# tenacitas.net
KiCad netlist of a schematic drawn in EAGLE
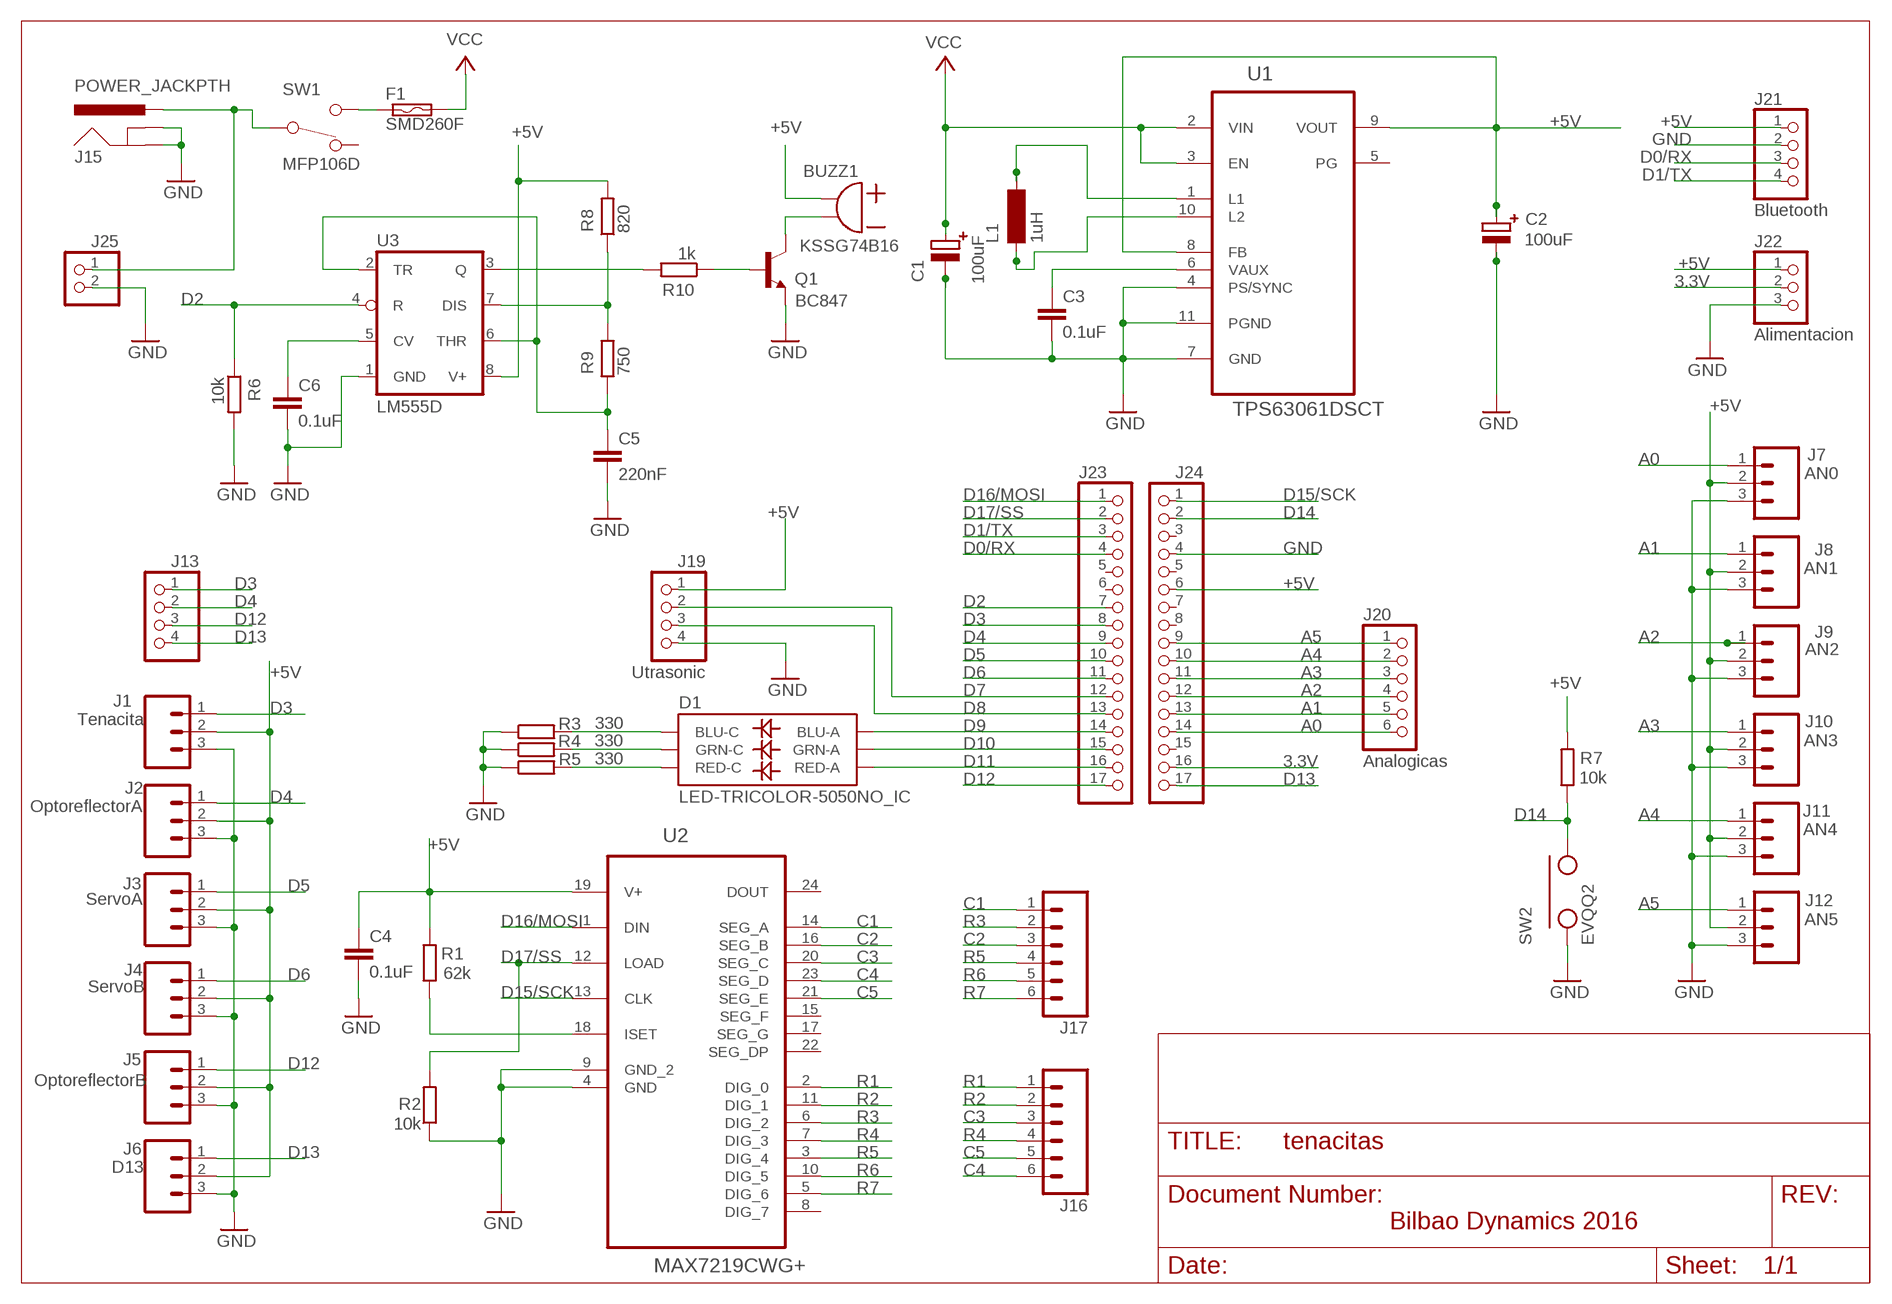
[diagram p0: schematic, sheet 1]

(export (version "E")
  (design (tool "Eeschema 10.0.6"))
  (components
    (comp (ref "BUZZ1")
      (value "KSSG74B16")
      (footprint "eagle-import:KSSG74B16")
      (libsource (lib "eagle-import") (part "KSSG74B16"))
    )
    (comp (ref "C1")
      (value "100uF")
      (footprint "eagle-import:EDK107M016A9G")
      (libsource (lib "eagle-import") (part "EDK107M016A9G"))
    )
    (comp (ref "C2")
      (value "100uF")
      (footprint "eagle-import:EDK107M016A9G")
      (libsource (lib "eagle-import") (part "EDK107M016A9G"))
    )
    (comp (ref "C3")
      (value "0.1uF")
      (footprint "eagle-import:C0805")
      (libsource (lib "eagle-import") (part "C-EUC0805"))
    )
    (comp (ref "C4")
      (value "0.1uF")
      (footprint "eagle-import:C0805")
      (libsource (lib "eagle-import") (part "C-EUC0805"))
    )
    (comp (ref "C5")
      (value "220nF")
      (footprint "eagle-import:C0805")
      (libsource (lib "eagle-import") (part "C-EUC0805"))
    )
    (comp (ref "C6")
      (value "0.1uF")
      (footprint "eagle-import:C0805")
      (libsource (lib "eagle-import") (part "C-EUC0805"))
    )
    (comp (ref "D1")
      (value "LED-TRICOLOR-5050NO_IC")
      (footprint "eagle-import:LED-TRICOLOR-5050")
      (libsource (lib "eagle-import") (part "LED-TRICOLOR-5050NO_IC"))
    )
    (comp (ref "F1")
      (value "SMD260F")
      (footprint "eagle-import:SMD050F")
      (libsource (lib "eagle-import") (part "SMDF260"))
    )
    (comp (ref "J1")
      (value "Tenacita")
      (footprint "eagle-import:1X03")
      (libsource (lib "eagle-import") (part "M03PTH"))
    )
    (comp (ref "J2")
      (value "OptoreflectorA")
      (footprint "eagle-import:1X03")
      (libsource (lib "eagle-import") (part "M03PTH"))
    )
    (comp (ref "J3")
      (value "ServoA")
      (footprint "eagle-import:1X03")
      (libsource (lib "eagle-import") (part "M03PTH"))
    )
    (comp (ref "J4")
      (value "ServoB")
      (footprint "eagle-import:1X03")
      (libsource (lib "eagle-import") (part "M03PTH"))
    )
    (comp (ref "J5")
      (value "OptoreflectorB")
      (footprint "eagle-import:1X03")
      (libsource (lib "eagle-import") (part "M03PTH"))
    )
    (comp (ref "J6")
      (value "D13")
      (footprint "eagle-import:1X03")
      (libsource (lib "eagle-import") (part "M03PTH"))
    )
    (comp (ref "J7")
      (value "AN0")
      (footprint "eagle-import:1X03")
      (libsource (lib "eagle-import") (part "M03PTH"))
    )
    (comp (ref "J8")
      (value "AN1")
      (footprint "eagle-import:1X03")
      (libsource (lib "eagle-import") (part "M03PTH"))
    )
    (comp (ref "J9")
      (value "AN2")
      (footprint "eagle-import:1X03")
      (libsource (lib "eagle-import") (part "M03PTH"))
    )
    (comp (ref "J10")
      (value "AN3")
      (footprint "eagle-import:1X03")
      (libsource (lib "eagle-import") (part "M03PTH"))
    )
    (comp (ref "J11")
      (value "AN4")
      (footprint "eagle-import:1X03")
      (libsource (lib "eagle-import") (part "M03PTH"))
    )
    (comp (ref "J12")
      (value "AN5")
      (footprint "eagle-import:1X03")
      (libsource (lib "eagle-import") (part "M03PTH"))
    )
    (comp (ref "J13")
      (value "PINHD-1X4")
      (footprint "eagle-import:1X04")
      (libsource (lib "eagle-import") (part "PINHD-1X4"))
    )
    (comp (ref "J15")
      (value "POWER_JACKPTH")
      (footprint "eagle-import:POWER_JACK_PTH")
      (libsource (lib "eagle-import") (part "POWER_JACKPTH"))
    )
    (comp (ref "J16")
      (value "M06SILK_FEMALE_PTH")
      (footprint "eagle-import:1X06")
      (libsource (lib "eagle-import") (part "M06SILK_FEMALE_PTH"))
    )
    (comp (ref "J17")
      (value "M06SILK_FEMALE_PTH")
      (footprint "eagle-import:1X06")
      (libsource (lib "eagle-import") (part "M06SILK_FEMALE_PTH"))
    )
    (comp (ref "J19")
      (value "Utrasonic")
      (footprint "eagle-import:1X04")
      (libsource (lib "eagle-import") (part "PINHD-1X4"))
    )
    (comp (ref "J20")
      (value "Analogicas")
      (footprint "eagle-import:1X06")
      (libsource (lib "eagle-import") (part "PINHD-1X6"))
    )
    (comp (ref "J21")
      (value "Bluetooth")
      (footprint "eagle-import:1X04")
      (libsource (lib "eagle-import") (part "PINHD-1X4"))
    )
    (comp (ref "J22")
      (value "Alimentacion")
      (footprint "eagle-import:1X03")
      (libsource (lib "eagle-import") (part "PINHD-1X3"))
    )
    (comp (ref "J23")
      (value "PINHD-1X17")
      (footprint "eagle-import:1X17")
      (libsource (lib "eagle-import") (part "PINHD-1X17"))
    )
    (comp (ref "J24")
      (value "PINHD-1X17")
      (footprint "eagle-import:1X17")
      (libsource (lib "eagle-import") (part "PINHD-1X17"))
    )
    (comp (ref "J25")
      (value "PINHD-1X2")
      (footprint "eagle-import:1X02")
      (libsource (lib "eagle-import") (part "PINHD-1X2"))
    )
    (comp (ref "L1")
      (value "1uH")
      (footprint "eagle-import:MCSDRH73B")
      (libsource (lib "eagle-import") (part "MCSDRH73B"))
    )
    (comp (ref "Q1")
      (value "BC847")
      (footprint "eagle-import:SOT23")
      (libsource (lib "eagle-import") (part "BC847"))
    )
    (comp (ref "R1")
      (value "62k")
      (footprint "eagle-import:R0805")
      (libsource (lib "eagle-import") (part "R-EU_R0805"))
    )
    (comp (ref "R2")
      (value "10k")
      (footprint "eagle-import:R0805")
      (libsource (lib "eagle-import") (part "R-EU_R0805"))
    )
    (comp (ref "R3")
      (value "330")
      (footprint "eagle-import:R0805")
      (libsource (lib "eagle-import") (part "R-EU_R0805"))
    )
    (comp (ref "R4")
      (value "330")
      (footprint "eagle-import:R0805")
      (libsource (lib "eagle-import") (part "R-EU_R0805"))
    )
    (comp (ref "R5")
      (value "330")
      (footprint "eagle-import:R0805")
      (libsource (lib "eagle-import") (part "R-EU_R0805"))
    )
    (comp (ref "R6")
      (value "10k")
      (footprint "eagle-import:R0805")
      (libsource (lib "eagle-import") (part "R-EU_R0805"))
    )
    (comp (ref "R7")
      (value "10k")
      (footprint "eagle-import:R0805")
      (libsource (lib "eagle-import") (part "R-EU_R0805"))
    )
    (comp (ref "R8")
      (value "820")
      (footprint "eagle-import:R0805")
      (libsource (lib "eagle-import") (part "R-EU_R0805"))
    )
    (comp (ref "R9")
      (value "750")
      (footprint "eagle-import:R0805")
      (libsource (lib "eagle-import") (part "R-EU_R0805"))
    )
    (comp (ref "R10")
      (value "1k")
      (footprint "eagle-import:R0805")
      (libsource (lib "eagle-import") (part "R-EU_R0805"))
    )
    (comp (ref "SW1")
      (value "MFP106D")
      (footprint "eagle-import:MFP106D")
      (libsource (lib "eagle-import") (part "MFP106D"))
    )
    (comp (ref "SW2")
      (value "EVQQ2")
      (footprint "eagle-import:JAEGGER_MKII_EVQQ2")
      (libsource (lib "eagle-import") (part "JAEGGER_MKII_EVQQ2"))
    )
    (comp (ref "U1")
      (value "TPS63061DSCT")
      (footprint "eagle-import:SON50P300X300X80-11N")
      (libsource (lib "eagle-import") (part "TPS63061DSCT"))
    )
    (comp (ref "U2")
      (value "MAX7219CWG+")
      (footprint "eagle-import:SOIC127P1032X265-24N")
      (libsource (lib "eagle-import") (part "MAX7219CWG+"))
    )
    (comp (ref "U3")
      (value "LM555D")
      (footprint "eagle-import:SO08")
      (libsource (lib "eagle-import") (part "555DLM"))
    )
  )
  (nets
    (net (code "1") (name "/+5V") (class "Default")
      (node (ref "BUZZ1") (pin "P$2") (pinfunction "2_P$2") (pintype "passive"))
      (node (ref "BUZZ1") (pin "P$3") (pinfunction "2_P$3") (pintype "passive"))
      (node (ref "C2") (pin "1") (pinfunction "1_1") (pintype "passive"))
      (node (ref "C4") (pin "1") (pinfunction "1_1") (pintype "passive"))
      (node (ref "J1") (pin "2") (pinfunction "2_2") (pintype "passive"))
      (node (ref "J10") (pin "2") (pinfunction "2_2") (pintype "passive"))
      (node (ref "J11") (pin "2") (pinfunction "2_2") (pintype "passive"))
      (node (ref "J12") (pin "2") (pinfunction "2_2") (pintype "passive"))
      (node (ref "J19") (pin "1") (pinfunction "1_1") (pintype "passive"))
      (node (ref "J2") (pin "2") (pinfunction "2_2") (pintype "passive"))
      (node (ref "J21") (pin "1") (pinfunction "1_1") (pintype "passive"))
      (node (ref "J22") (pin "1") (pinfunction "1_1") (pintype "passive"))
      (node (ref "J24") (pin "6") (pinfunction "6_6") (pintype "passive"))
      (node (ref "J3") (pin "2") (pinfunction "2_2") (pintype "passive"))
      (node (ref "J4") (pin "2") (pinfunction "2_2") (pintype "passive"))
      (node (ref "J5") (pin "2") (pinfunction "2_2") (pintype "passive"))
      (node (ref "J6") (pin "2") (pinfunction "2_2") (pintype "passive"))
      (node (ref "J7") (pin "2") (pinfunction "2_2") (pintype "passive"))
      (node (ref "J8") (pin "2") (pinfunction "2_2") (pintype "passive"))
      (node (ref "J9") (pin "2") (pinfunction "2_2") (pintype "passive"))
      (node (ref "R1") (pin "2") (pinfunction "2_2") (pintype "passive"))
      (node (ref "R7") (pin "2") (pinfunction "2_2") (pintype "passive"))
      (node (ref "R8") (pin "2") (pinfunction "2_2") (pintype "passive"))
      (node (ref "U1") (pin "8") (pinfunction "FB_8") (pintype "input"))
      (node (ref "U1") (pin "9") (pinfunction "VOUT_9") (pintype "output"))
      (node (ref "U2") (pin "19") (pinfunction "V+_19") (pintype "power_in"))
      (node (ref "U3") (pin "8") (pinfunction "V+_8") (pintype "power_in"))
    )
    (net (code "2") (name "/3.3V") (class "Default")
      (node (ref "J22") (pin "2") (pinfunction "2_2") (pintype "passive"))
      (node (ref "J24") (pin "16") (pinfunction "16_16") (pintype "passive"))
    )
    (net (code "3") (name "/A0") (class "Default")
      (node (ref "J20") (pin "6") (pinfunction "6_6") (pintype "passive"))
      (node (ref "J24") (pin "14") (pinfunction "14_14") (pintype "passive"))
      (node (ref "J7") (pin "1") (pinfunction "1_1") (pintype "passive"))
    )
    (net (code "4") (name "/A1") (class "Default")
      (node (ref "J20") (pin "5") (pinfunction "5_5") (pintype "passive"))
      (node (ref "J24") (pin "13") (pinfunction "13_13") (pintype "passive"))
      (node (ref "J8") (pin "1") (pinfunction "1_1") (pintype "passive"))
    )
    (net (code "5") (name "/A2") (class "Default")
      (node (ref "J20") (pin "4") (pinfunction "4_4") (pintype "passive"))
      (node (ref "J24") (pin "12") (pinfunction "12_12") (pintype "passive"))
      (node (ref "J9") (pin "1") (pinfunction "1_1") (pintype "passive"))
    )
    (net (code "6") (name "/A3") (class "Default")
      (node (ref "J10") (pin "1") (pinfunction "1_1") (pintype "passive"))
      (node (ref "J20") (pin "3") (pinfunction "3_3") (pintype "passive"))
      (node (ref "J24") (pin "11") (pinfunction "11_11") (pintype "passive"))
    )
    (net (code "7") (name "/A4") (class "Default")
      (node (ref "J11") (pin "1") (pinfunction "1_1") (pintype "passive"))
      (node (ref "J20") (pin "2") (pinfunction "2_2") (pintype "passive"))
      (node (ref "J24") (pin "10") (pinfunction "10_10") (pintype "passive"))
    )
    (net (code "8") (name "/A5") (class "Default")
      (node (ref "J12") (pin "1") (pinfunction "1_1") (pintype "passive"))
      (node (ref "J20") (pin "1") (pinfunction "1_1") (pintype "passive"))
      (node (ref "J24") (pin "9") (pinfunction "9_9") (pintype "passive"))
    )
    (net (code "9") (name "/C1") (class "Default")
      (node (ref "J17") (pin "1") (pinfunction "1_1") (pintype "passive"))
      (node (ref "U2") (pin "14") (pinfunction "SEG_A_14") (pintype "output"))
    )
    (net (code "10") (name "/C2") (class "Default")
      (node (ref "J17") (pin "3") (pinfunction "3_3") (pintype "passive"))
      (node (ref "U2") (pin "16") (pinfunction "SEG_B_16") (pintype "output"))
    )
    (net (code "11") (name "/C3") (class "Default")
      (node (ref "J16") (pin "3") (pinfunction "3_3") (pintype "passive"))
      (node (ref "U2") (pin "20") (pinfunction "SEG_C_20") (pintype "output"))
    )
    (net (code "12") (name "/C4") (class "Default")
      (node (ref "J16") (pin "6") (pinfunction "6_6") (pintype "passive"))
      (node (ref "U2") (pin "23") (pinfunction "SEG_D_23") (pintype "output"))
    )
    (net (code "13") (name "/C5") (class "Default")
      (node (ref "J16") (pin "5") (pinfunction "5_5") (pintype "passive"))
      (node (ref "U2") (pin "21") (pinfunction "SEG_E_21") (pintype "output"))
    )
    (net (code "14") (name "/D0{slash}RX") (class "Default")
      (node (ref "J21") (pin "3") (pinfunction "3_3") (pintype "passive"))
      (node (ref "J23") (pin "4") (pinfunction "4_4") (pintype "passive"))
    )
    (net (code "15") (name "/D1{slash}TX") (class "Default")
      (node (ref "J21") (pin "4") (pinfunction "4_4") (pintype "passive"))
      (node (ref "J23") (pin "3") (pinfunction "3_3") (pintype "passive"))
    )
    (net (code "16") (name "/D2") (class "Default")
      (node (ref "J23") (pin "7") (pinfunction "7_7") (pintype "passive"))
      (node (ref "R6") (pin "1") (pinfunction "1_1") (pintype "passive"))
      (node (ref "U3") (pin "4") (pinfunction "R_4") (pintype "input"))
    )
    (net (code "17") (name "/D3") (class "Default")
      (node (ref "J1") (pin "1") (pinfunction "1_1") (pintype "passive"))
      (node (ref "J13") (pin "1") (pinfunction "1_1") (pintype "passive"))
      (node (ref "J23") (pin "8") (pinfunction "8_8") (pintype "passive"))
    )
    (net (code "18") (name "/D4") (class "Default")
      (node (ref "J13") (pin "2") (pinfunction "2_2") (pintype "passive"))
      (node (ref "J2") (pin "1") (pinfunction "1_1") (pintype "passive"))
      (node (ref "J23") (pin "9") (pinfunction "9_9") (pintype "passive"))
    )
    (net (code "19") (name "/D5") (class "Default")
      (node (ref "J23") (pin "10") (pinfunction "10_10") (pintype "passive"))
      (node (ref "J3") (pin "1") (pinfunction "1_1") (pintype "passive"))
    )
    (net (code "20") (name "/D6") (class "Default")
      (node (ref "J23") (pin "11") (pinfunction "11_11") (pintype "passive"))
      (node (ref "J4") (pin "1") (pinfunction "1_1") (pintype "passive"))
    )
    (net (code "21") (name "/D7") (class "Default")
      (node (ref "J19") (pin "2") (pinfunction "2_2") (pintype "passive"))
      (node (ref "J23") (pin "12") (pinfunction "12_12") (pintype "passive"))
    )
    (net (code "22") (name "/D8") (class "Default")
      (node (ref "J19") (pin "3") (pinfunction "3_3") (pintype "passive"))
      (node (ref "J23") (pin "13") (pinfunction "13_13") (pintype "passive"))
    )
    (net (code "23") (name "/D9") (class "Default")
      (node (ref "D1") (pin "3") (pinfunction "BLU-A_3") (pintype "bidirectional"))
      (node (ref "J23") (pin "14") (pinfunction "14_14") (pintype "passive"))
    )
    (net (code "24") (name "/D10") (class "Default")
      (node (ref "D1") (pin "1") (pinfunction "GRN-A_1") (pintype "bidirectional"))
      (node (ref "J23") (pin "15") (pinfunction "15_15") (pintype "passive"))
    )
    (net (code "25") (name "/D11") (class "Default")
      (node (ref "D1") (pin "2") (pinfunction "RED-A_2") (pintype "bidirectional"))
      (node (ref "J23") (pin "16") (pinfunction "16_16") (pintype "passive"))
    )
    (net (code "26") (name "/D12") (class "Default")
      (node (ref "J13") (pin "3") (pinfunction "3_3") (pintype "passive"))
      (node (ref "J23") (pin "17") (pinfunction "17_17") (pintype "passive"))
      (node (ref "J5") (pin "1") (pinfunction "1_1") (pintype "passive"))
    )
    (net (code "27") (name "/D13") (class "Default")
      (node (ref "J13") (pin "4") (pinfunction "4_4") (pintype "passive"))
      (node (ref "J24") (pin "17") (pinfunction "17_17") (pintype "passive"))
      (node (ref "J6") (pin "1") (pinfunction "1_1") (pintype "passive"))
    )
    (net (code "28") (name "/D14") (class "Default")
      (node (ref "J24") (pin "2") (pinfunction "2_2") (pintype "passive"))
      (node (ref "R7") (pin "1") (pinfunction "1_1") (pintype "passive"))
      (node (ref "SW2") (pin "P$1") (pinfunction "P$2_P$1") (pintype "passive"))
      (node (ref "SW2") (pin "P$4") (pinfunction "P$2_P$4") (pintype "passive"))
    )
    (net (code "29") (name "/D15{slash}SCK") (class "Default")
      (node (ref "J24") (pin "1") (pinfunction "1_1") (pintype "passive"))
      (node (ref "U2") (pin "13") (pinfunction "CLK_13") (pintype "input"))
    )
    (net (code "30") (name "/D16{slash}MOSI") (class "Default")
      (node (ref "J23") (pin "1") (pinfunction "1_1") (pintype "passive"))
      (node (ref "U2") (pin "1") (pinfunction "DIN_1") (pintype "input"))
    )
    (net (code "31") (name "/D17{slash}SS") (class "Default")
      (node (ref "J23") (pin "2") (pinfunction "2_2") (pintype "passive"))
      (node (ref "R2") (pin "2") (pinfunction "2_2") (pintype "passive"))
      (node (ref "U2") (pin "12") (pinfunction "LOAD_12") (pintype "input"))
    )
    (net (code "32") (name "/R1") (class "Default")
      (node (ref "J16") (pin "1") (pinfunction "1_1") (pintype "passive"))
      (node (ref "U2") (pin "2") (pinfunction "DIG_0_2") (pintype "output"))
    )
    (net (code "33") (name "/R2") (class "Default")
      (node (ref "J16") (pin "2") (pinfunction "2_2") (pintype "passive"))
      (node (ref "U2") (pin "11") (pinfunction "DIG_1_11") (pintype "output"))
    )
    (net (code "34") (name "/R3") (class "Default")
      (node (ref "J17") (pin "2") (pinfunction "2_2") (pintype "passive"))
      (node (ref "U2") (pin "6") (pinfunction "DIG_2_6") (pintype "output"))
    )
    (net (code "35") (name "/R4") (class "Default")
      (node (ref "J16") (pin "4") (pinfunction "4_4") (pintype "passive"))
      (node (ref "U2") (pin "7") (pinfunction "DIG_3_7") (pintype "output"))
    )
    (net (code "36") (name "/R5") (class "Default")
      (node (ref "J17") (pin "4") (pinfunction "4_4") (pintype "passive"))
      (node (ref "U2") (pin "3") (pinfunction "DIG_4_3") (pintype "output"))
    )
    (net (code "37") (name "/R6") (class "Default")
      (node (ref "J17") (pin "5") (pinfunction "5_5") (pintype "passive"))
      (node (ref "U2") (pin "10") (pinfunction "DIG_5_10") (pintype "output"))
    )
    (net (code "38") (name "/R7") (class "Default")
      (node (ref "J17") (pin "6") (pinfunction "6_6") (pintype "passive"))
      (node (ref "U2") (pin "5") (pinfunction "DIG_6_5") (pintype "output"))
    )
    (net (code "39") (name "GND") (class "Default")
      (node (ref "C1") (pin "2") (pinfunction "2_2") (pintype "passive"))
      (node (ref "C2") (pin "2") (pinfunction "2_2") (pintype "passive"))
      (node (ref "C3") (pin "2") (pinfunction "2_2") (pintype "passive"))
      (node (ref "C4") (pin "2") (pinfunction "2_2") (pintype "passive"))
      (node (ref "C5") (pin "2") (pinfunction "2_2") (pintype "passive"))
      (node (ref "C6") (pin "2") (pinfunction "2_2") (pintype "passive"))
      (node (ref "J1") (pin "3") (pinfunction "3_3") (pintype "passive"))
      (node (ref "J10") (pin "3") (pinfunction "3_3") (pintype "passive"))
      (node (ref "J11") (pin "3") (pinfunction "3_3") (pintype "passive"))
      (node (ref "J12") (pin "3") (pinfunction "3_3") (pintype "passive"))
      (node (ref "J15") (pin "GND") (pinfunction "GND_GND") (pintype "bidirectional"))
      (node (ref "J15") (pin "GNDBREAK") (pinfunction "GNDBREAK_GNDBREAK") (pintype "bidirectional"))
      (node (ref "J19") (pin "4") (pinfunction "4_4") (pintype "passive"))
      (node (ref "J2") (pin "3") (pinfunction "3_3") (pintype "passive"))
      (node (ref "J21") (pin "2") (pinfunction "2_2") (pintype "passive"))
      (node (ref "J22") (pin "3") (pinfunction "3_3") (pintype "passive"))
      (node (ref "J24") (pin "4") (pinfunction "4_4") (pintype "passive"))
      (node (ref "J25") (pin "2") (pinfunction "2_2") (pintype "passive"))
      (node (ref "J3") (pin "3") (pinfunction "3_3") (pintype "passive"))
      (node (ref "J4") (pin "3") (pinfunction "3_3") (pintype "passive"))
      (node (ref "J5") (pin "3") (pinfunction "3_3") (pintype "passive"))
      (node (ref "J6") (pin "3") (pinfunction "3_3") (pintype "passive"))
      (node (ref "J7") (pin "3") (pinfunction "3_3") (pintype "passive"))
      (node (ref "J8") (pin "3") (pinfunction "3_3") (pintype "passive"))
      (node (ref "J9") (pin "3") (pinfunction "3_3") (pintype "passive"))
      (node (ref "Q1") (pin "2") (pinfunction "E_2") (pintype "passive"))
      (node (ref "R2") (pin "1") (pinfunction "1_1") (pintype "passive"))
      (node (ref "R3") (pin "1") (pinfunction "1_1") (pintype "passive"))
      (node (ref "R4") (pin "1") (pinfunction "1_1") (pintype "passive"))
      (node (ref "R5") (pin "1") (pinfunction "1_1") (pintype "passive"))
      (node (ref "R6") (pin "2") (pinfunction "2_2") (pintype "passive"))
      (node (ref "SW2") (pin "P$2") (pinfunction "P$1_P$2") (pintype "passive"))
      (node (ref "SW2") (pin "P$3") (pinfunction "P$1_P$3") (pintype "passive"))
      (node (ref "U1") (pin "11") (pinfunction "PGND_11") (pintype "passive"))
      (node (ref "U1") (pin "4") (pinfunction "PS/SYNC_4") (pintype "input"))
      (node (ref "U1") (pin "7") (pinfunction "GND_7") (pintype "passive"))
      (node (ref "U2") (pin "4") (pinfunction "GND_4") (pintype "passive"))
      (node (ref "U2") (pin "9") (pinfunction "GND_2_9") (pintype "passive"))
      (node (ref "U3") (pin "1") (pinfunction "GND_1") (pintype "power_in"))
    )
    (net (code "40") (name "Net-(D1-BLU-C)") (class "Default")
      (node (ref "D1") (pin "4") (pinfunction "BLU-C_4") (pintype "bidirectional"))
      (node (ref "R3") (pin "2") (pinfunction "2_2") (pintype "passive"))
    )
    (net (code "41") (name "Net-(D1-GRN-C)") (class "Default")
      (node (ref "D1") (pin "6") (pinfunction "GRN-C_6") (pintype "bidirectional"))
      (node (ref "R4") (pin "2") (pinfunction "2_2") (pintype "passive"))
    )
    (net (code "42") (name "Net-(D1-RED-C)") (class "Default")
      (node (ref "D1") (pin "5") (pinfunction "RED-C_5") (pintype "bidirectional"))
      (node (ref "R5") (pin "2") (pinfunction "2_2") (pintype "passive"))
    )
    (net (code "43") (name "Net-(F1-Pad1)") (class "Default")
      (node (ref "F1") (pin "1") (pinfunction "1_1") (pintype "passive"))
      (node (ref "SW1") (pin "2") (pinfunction "2_2") (pintype "passive"))
    )
    (net (code "44") (name "Net-(J15-PadPWR)") (class "Default")
      (node (ref "J15") (pin "PWR") (pinfunction "PWR_PWR") (pintype "bidirectional"))
      (node (ref "J25") (pin "1") (pinfunction "1_1") (pintype "passive"))
      (node (ref "SW1") (pin "COM") (pinfunction "COM_COM") (pintype "passive"))
    )
    (net (code "45") (name "Net-(L1-P$1)") (class "Default")
      (node (ref "L1") (pin "1") (pinfunction "P$1_1") (pintype "passive"))
      (node (ref "U1") (pin "10") (pinfunction "L2_10") (pintype "input"))
    )
    (net (code "46") (name "Net-(L1-P$2)") (class "Default")
      (node (ref "L1") (pin "2") (pinfunction "P$2_2") (pintype "passive"))
      (node (ref "U1") (pin "1") (pinfunction "L1_1") (pintype "input"))
    )
    (net (code "47") (name "Net-(Q1-B)") (class "Default")
      (node (ref "Q1") (pin "1") (pinfunction "B_1") (pintype "passive"))
      (node (ref "R10") (pin "1") (pinfunction "1_1") (pintype "passive"))
    )
    (net (code "48") (name "Net-(Q1-C)") (class "Default")
      (node (ref "BUZZ1") (pin "P$1") (pinfunction "1_P$1") (pintype "passive"))
      (node (ref "BUZZ1") (pin "P$4") (pinfunction "1_P$4") (pintype "passive"))
      (node (ref "Q1") (pin "3") (pinfunction "C_3") (pintype "passive"))
    )
    (net (code "49") (name "Net-(U1-VAUX)") (class "Default")
      (node (ref "C3") (pin "1") (pinfunction "1_1") (pintype "passive"))
      (node (ref "U1") (pin "6") (pinfunction "VAUX_6") (pintype "passive"))
    )
    (net (code "50") (name "Net-(U2-ISET)") (class "Default")
      (node (ref "R1") (pin "1") (pinfunction "1_1") (pintype "passive"))
      (node (ref "U2") (pin "18") (pinfunction "ISET_18") (pintype "input"))
    )
    (net (code "51") (name "Net-(U3-CV)") (class "Default")
      (node (ref "C6") (pin "1") (pinfunction "1_1") (pintype "passive"))
      (node (ref "U3") (pin "5") (pinfunction "CV_5") (pintype "input"))
    )
    (net (code "52") (name "Net-(U3-DIS)") (class "Default")
      (node (ref "R8") (pin "1") (pinfunction "1_1") (pintype "passive"))
      (node (ref "R9") (pin "2") (pinfunction "2_2") (pintype "passive"))
      (node (ref "U3") (pin "7") (pinfunction "DIS_7") (pintype "input"))
    )
    (net (code "53") (name "Net-(U3-Q)") (class "Default")
      (node (ref "R10") (pin "2") (pinfunction "2_2") (pintype "passive"))
      (node (ref "U3") (pin "3") (pinfunction "Q_3") (pintype "output"))
    )
    (net (code "54") (name "Net-(U3-THR)") (class "Default")
      (node (ref "C5") (pin "1") (pinfunction "1_1") (pintype "passive"))
      (node (ref "R9") (pin "1") (pinfunction "1_1") (pintype "passive"))
      (node (ref "U3") (pin "2") (pinfunction "TR_2") (pintype "input"))
      (node (ref "U3") (pin "6") (pinfunction "THR_6") (pintype "input"))
    )
    (net (code "55") (name "VCC") (class "Default")
      (node (ref "C1") (pin "1") (pinfunction "1_1") (pintype "passive"))
      (node (ref "F1") (pin "2") (pinfunction "2_2") (pintype "passive"))
      (node (ref "U1") (pin "2") (pinfunction "VIN_2") (pintype "power_in"))
      (node (ref "U1") (pin "3") (pinfunction "EN_3") (pintype "input"))
    )
    (net (code "56") (name "unconnected-(J23-Pad5)") (class "Default")
      (node (ref "J23") (pin "5") (pinfunction "5_5") (pintype "passive"))
    )
    (net (code "57") (name "unconnected-(J23-Pad6)") (class "Default")
      (node (ref "J23") (pin "6") (pinfunction "6_6") (pintype "passive"))
    )
    (net (code "58") (name "unconnected-(J24-Pad3)") (class "Default")
      (node (ref "J24") (pin "3") (pinfunction "3_3") (pintype "passive"))
    )
    (net (code "59") (name "unconnected-(J24-Pad5)") (class "Default")
      (node (ref "J24") (pin "5") (pinfunction "5_5") (pintype "passive"))
    )
    (net (code "60") (name "unconnected-(J24-Pad7)") (class "Default")
      (node (ref "J24") (pin "7") (pinfunction "7_7") (pintype "passive"))
    )
    (net (code "61") (name "unconnected-(J24-Pad8)") (class "Default")
      (node (ref "J24") (pin "8") (pinfunction "8_8") (pintype "passive"))
    )
    (net (code "62") (name "unconnected-(J24-Pad15)") (class "Default")
      (node (ref "J24") (pin "15") (pinfunction "15_15") (pintype "passive"))
    )
    (net (code "63") (name "unconnected-(SW1-Pad1)") (class "Default")
      (node (ref "SW1") (pin "1") (pinfunction "1_1") (pintype "passive"))
    )
    (net (code "64") (name "unconnected-(U1-PG-Pad5)") (class "Default")
      (node (ref "U1") (pin "5") (pinfunction "PG_5") (pintype "output"))
    )
    (net (code "65") (name "unconnected-(U2-DIG_7-Pad8)") (class "Default")
      (node (ref "U2") (pin "8") (pinfunction "DIG_7_8") (pintype "output"))
    )
    (net (code "66") (name "unconnected-(U2-DOUT-Pad24)") (class "Default")
      (node (ref "U2") (pin "24") (pinfunction "DOUT_24") (pintype "output"))
    )
    (net (code "67") (name "unconnected-(U2-SEG_DP-Pad22)") (class "Default")
      (node (ref "U2") (pin "22") (pinfunction "SEG_DP_22") (pintype "output"))
    )
    (net (code "68") (name "unconnected-(U2-SEG_F-Pad15)") (class "Default")
      (node (ref "U2") (pin "15") (pinfunction "SEG_F_15") (pintype "output"))
    )
    (net (code "69") (name "unconnected-(U2-SEG_G-Pad17)") (class "Default")
      (node (ref "U2") (pin "17") (pinfunction "SEG_G_17") (pintype "output"))
    )
  )
)
